# DetecteurSonnore.net
KiCad netlist of a schematic drawn in EAGLE
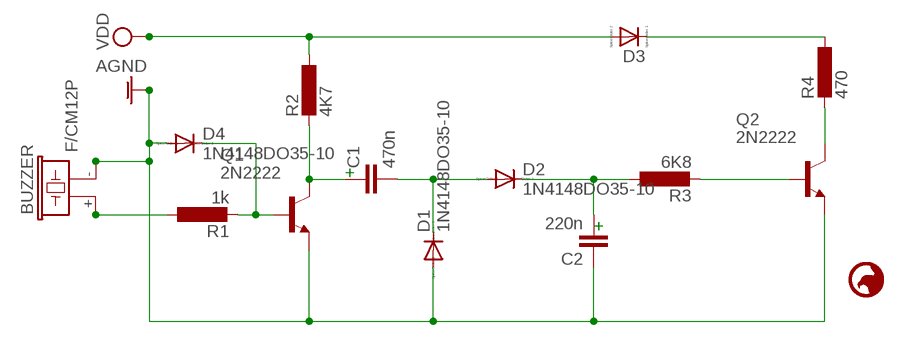
[diagram p0: schematic, sheet 1]

(export (version "E")
  (design (tool "Eeschema 10.0.6"))
  (components
    (comp (ref "BUZZER")
      (value "F/CM12P")
      (footprint "eagle-import:F_CM12P")
      (libsource (lib "eagle-import") (part "F/CM12P"))
    )
    (comp (ref "C1")
      (value "470n")
      (footprint "eagle-import:C7.5B3")
      (libsource (lib "eagle-import") (part "C7.5/3"))
    )
    (comp (ref "C2")
      (value "220n")
      (footprint "eagle-import:C7.5B3")
      (libsource (lib "eagle-import") (part "C7.5/3"))
    )
    (comp (ref "D1")
      (value "1N4148DO35-10")
      (footprint "eagle-import:DO35-10")
      (libsource (lib "eagle-import") (part "1N4148DO35-10"))
    )
    (comp (ref "D2")
      (value "1N4148DO35-10")
      (footprint "eagle-import:DO35-10")
      (libsource (lib "eagle-import") (part "1N4148DO35-10"))
    )
    (comp (ref "D3")
      (value "DIODE_E-DO35-7")
      (footprint "eagle-import:DIODE_DO35-7")
      (libsource (lib "eagle-import") (part "DIODE_E-DO35-7"))
    )
    (comp (ref "D4")
      (value "1N4148DO35-10")
      (footprint "eagle-import:DO35-10")
      (libsource (lib "eagle-import") (part "1N4148DO35-10"))
    )
    (comp (ref "Q1")
      (value "2N2222")
      (footprint "eagle-import:TO18")
      (libsource (lib "eagle-import") (part "2N2222"))
    )
    (comp (ref "Q2")
      (value "2N2222")
      (footprint "eagle-import:TO18")
      (libsource (lib "eagle-import") (part "2N2222"))
    )
    (comp (ref "R1")
      (value "1k")
      (footprint "eagle-import:0207_15")
      (libsource (lib "eagle-import") (part "L-EU0207/15"))
    )
    (comp (ref "R2")
      (value "4K7")
      (footprint "eagle-import:0207_15")
      (libsource (lib "eagle-import") (part "L-EU0207/15"))
    )
    (comp (ref "R3")
      (value "6K8")
      (footprint "eagle-import:0207_15")
      (libsource (lib "eagle-import") (part "L-EU0207/15"))
    )
    (comp (ref "R4")
      (value "470")
      (footprint "eagle-import:0207_15")
      (libsource (lib "eagle-import") (part "L-EU0207/15"))
    )
  )
  (nets
    (net (code "1") (name "AGND") (class "Default")
      (node (ref "BUZZER") (pin "-") (pinfunction "2_-") (pintype "passive"))
      (node (ref "C2") (pin "1") (pinfunction "1_1") (pintype "passive"))
      (node (ref "D1") (pin "A") (pinfunction "A_A") (pintype "passive"))
      (node (ref "D4") (pin "A") (pinfunction "A_A") (pintype "passive"))
      (node (ref "Q1") (pin "1") (pinfunction "E_1") (pintype "passive"))
      (node (ref "Q2") (pin "1") (pinfunction "E_1") (pintype "passive"))
    )
    (net (code "2") (name "Net-(BUZZER-1)") (class "Default")
      (node (ref "BUZZER") (pin "+") (pinfunction "1_+") (pintype "passive"))
      (node (ref "R1") (pin "1") (pinfunction "1_1") (pintype "passive"))
    )
    (net (code "3") (name "Net-(C1-Pad2)") (class "Default")
      (node (ref "C1") (pin "2") (pinfunction "2_2") (pintype "passive"))
      (node (ref "D1") (pin "C") (pinfunction "C_C") (pintype "passive"))
      (node (ref "D2") (pin "A") (pinfunction "A_A") (pintype "passive"))
    )
    (net (code "4") (name "Net-(C2-Pad2)") (class "Default")
      (node (ref "C2") (pin "2") (pinfunction "2_2") (pintype "passive"))
      (node (ref "D2") (pin "C") (pinfunction "C_C") (pintype "passive"))
      (node (ref "R3") (pin "1") (pinfunction "1_1") (pintype "passive"))
    )
    (net (code "5") (name "Net-(D3-A)") (class "Default")
      (node (ref "D3") (pin "C") (pinfunction "A_C") (pintype "passive"))
      (node (ref "R4") (pin "1") (pinfunction "1_1") (pintype "passive"))
    )
    (net (code "6") (name "Net-(Q1-B)") (class "Default")
      (node (ref "D4") (pin "C") (pinfunction "C_C") (pintype "passive"))
      (node (ref "Q1") (pin "2") (pinfunction "B_2") (pintype "passive"))
      (node (ref "R1") (pin "2") (pinfunction "2_2") (pintype "passive"))
    )
    (net (code "7") (name "Net-(Q1-C)") (class "Default")
      (node (ref "C1") (pin "1") (pinfunction "1_1") (pintype "passive"))
      (node (ref "Q1") (pin "3") (pinfunction "C_3") (pintype "passive"))
      (node (ref "R2") (pin "2") (pinfunction "2_2") (pintype "passive"))
    )
    (net (code "8") (name "Net-(Q2-B)") (class "Default")
      (node (ref "Q2") (pin "2") (pinfunction "B_2") (pintype "passive"))
      (node (ref "R3") (pin "2") (pinfunction "2_2") (pintype "passive"))
    )
    (net (code "9") (name "Net-(Q2-C)") (class "Default")
      (node (ref "Q2") (pin "3") (pinfunction "C_3") (pintype "passive"))
      (node (ref "R4") (pin "2") (pinfunction "2_2") (pintype "passive"))
    )
    (net (code "10") (name "VDD") (class "Default")
      (node (ref "D3") (pin "A") (pinfunction "C_A") (pintype "passive"))
      (node (ref "R2") (pin "1") (pinfunction "1_1") (pintype "passive"))
    )
  )
)
